# SCH_ESP-CellCore_USB_Interlock_RevA2_IMP.net
KiCad netlist of a schematic drawn in EasyEDA
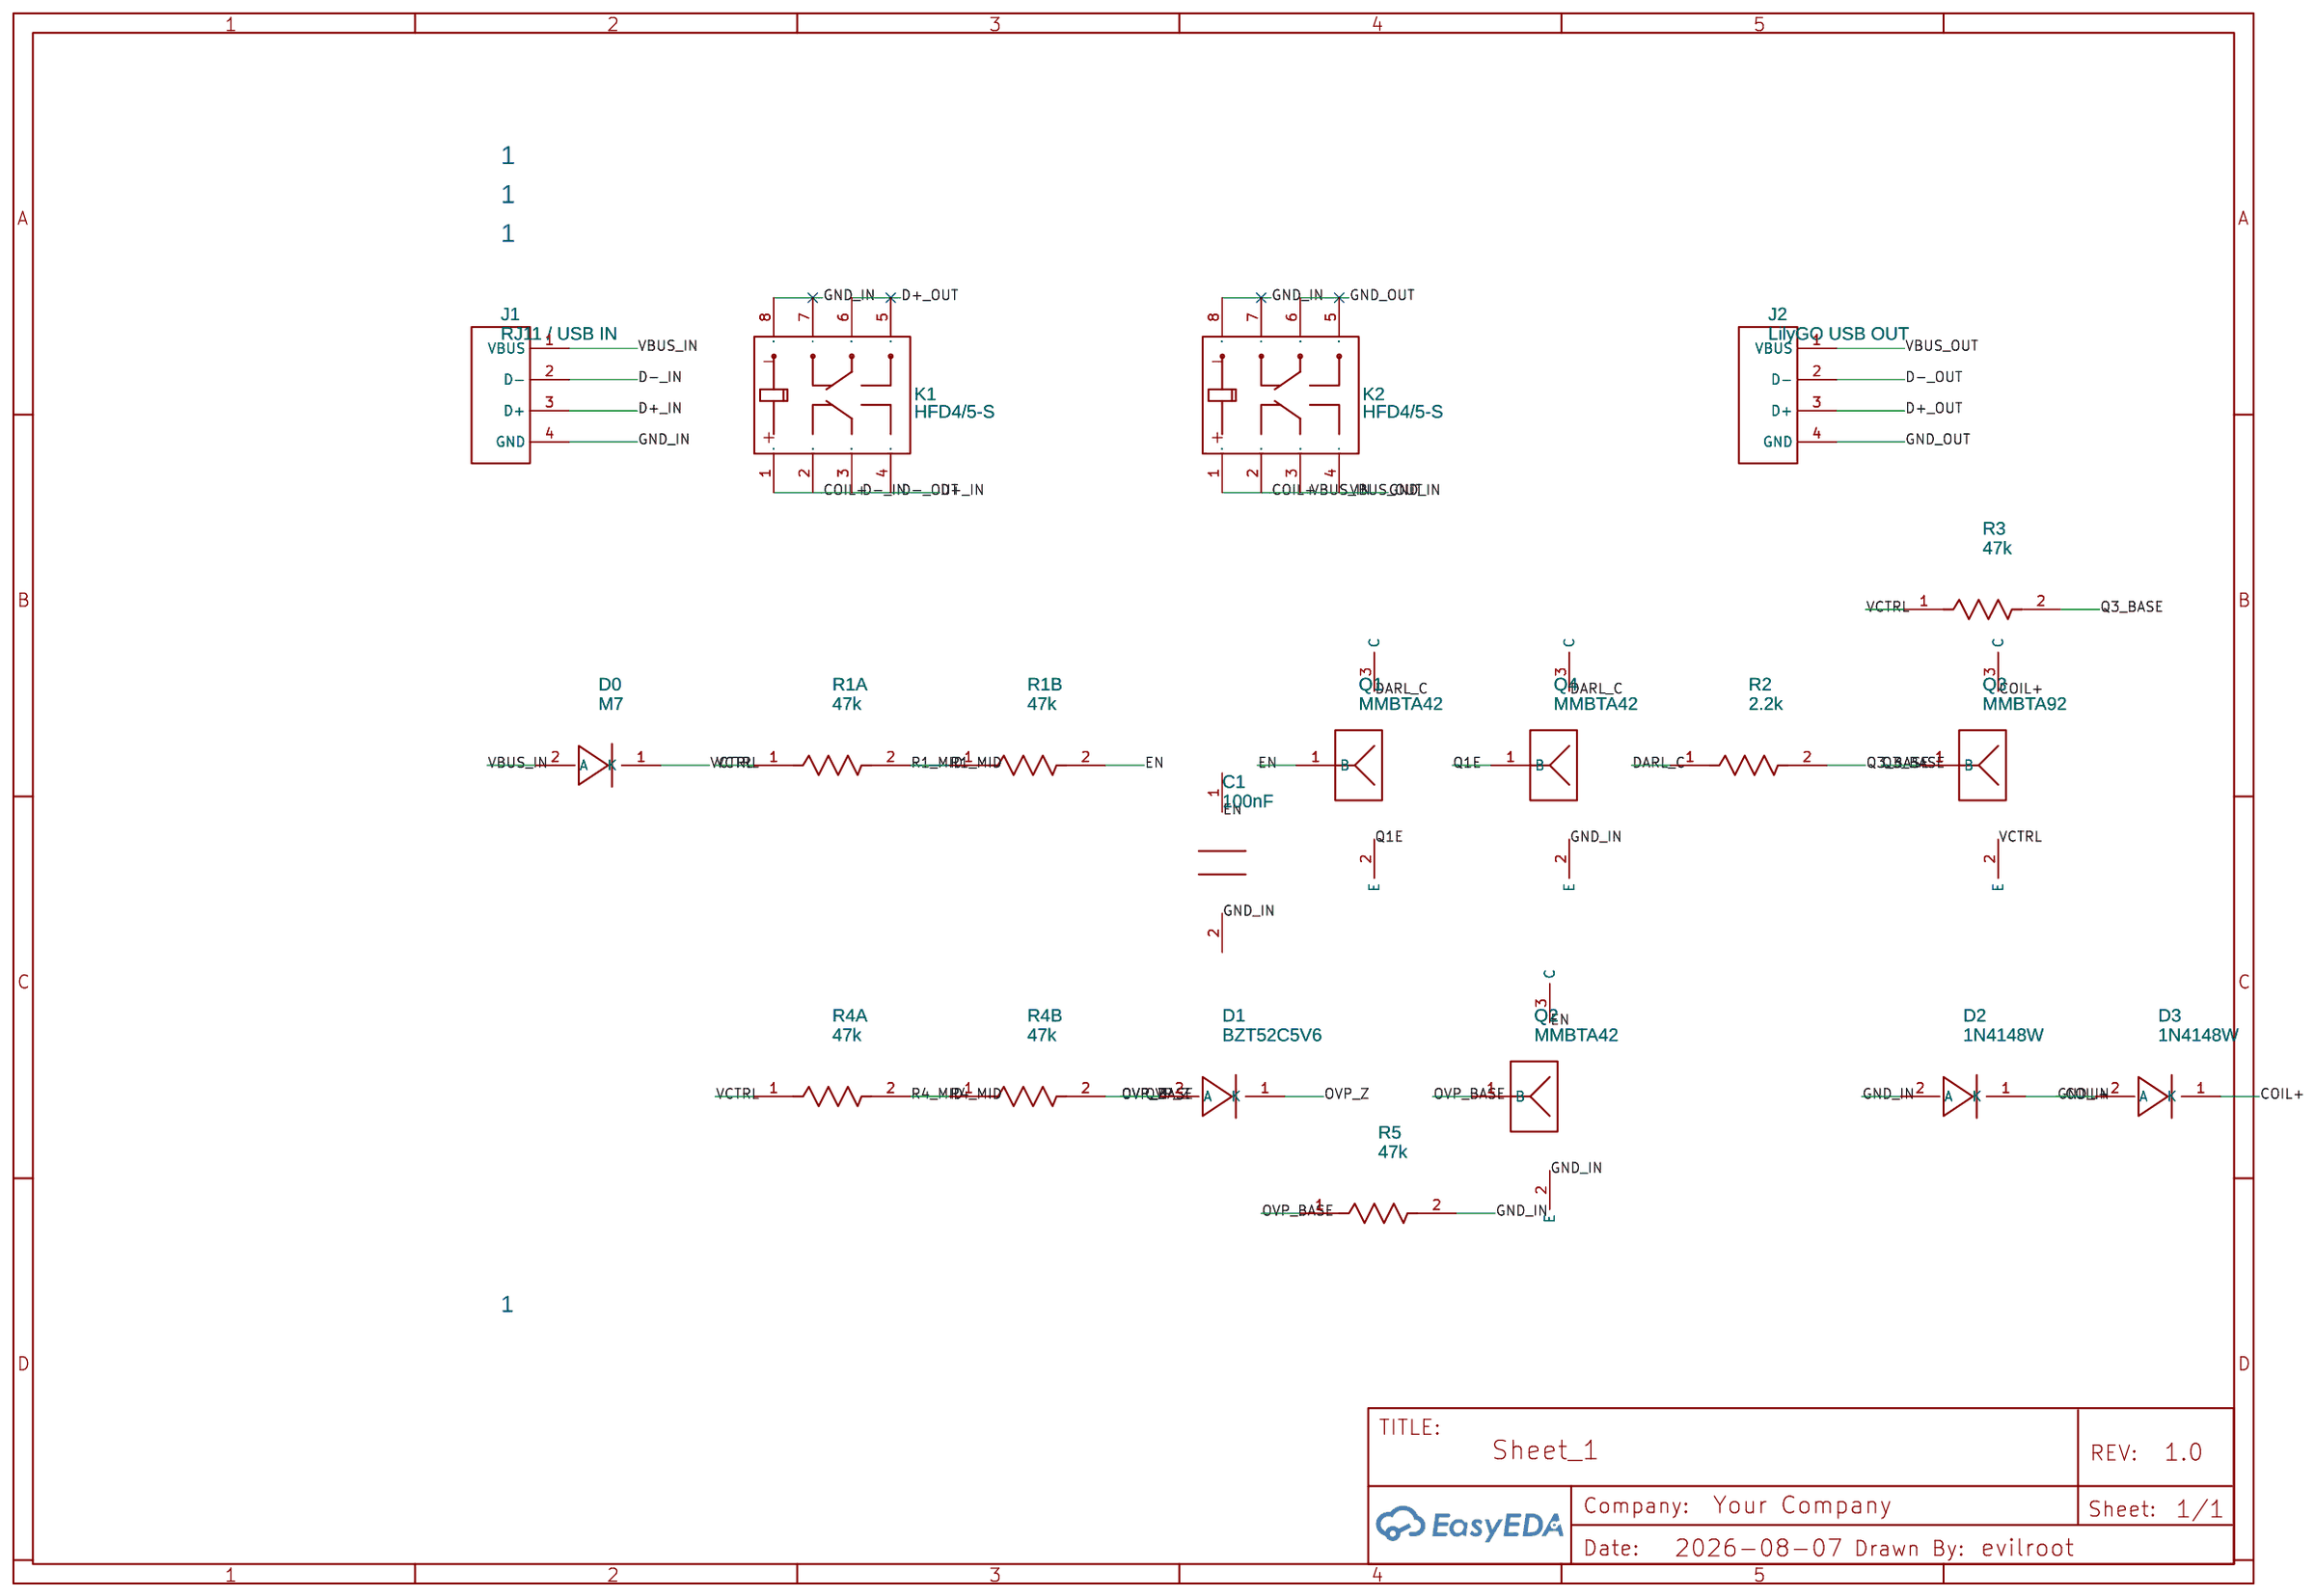
[diagram p0: schematic sheet]

(export (version "E")
  (design (tool "Eeschema 10.0.6"))
  (components
    (comp (ref "C1") (value "100nF") (libsource (lib "") (part "Unknown_620_-370")))
    (comp (ref "D0") (value "M7") (libsource (lib "") (part "Unknown_300_-420")))
    (comp (ref "D1") (value "BZT52C5V6") (libsource (lib "") (part "Unknown_620_-250")))
    (comp (ref "D2") (value "1N4148W") (libsource (lib "") (part "Unknown_1000_-250")))
    (comp (ref "D3") (value "1N4148W") (libsource (lib "") (part "Unknown_1100_-250")))
    (comp (ref "J1") (value "RJ11 / USB IN") (libsource (lib "") (part "Unknown_250_-610")))
    (comp (ref "J2") (value "LilyGO USB OUT") (libsource (lib "") (part "Unknown_900_-610")))
    (comp (ref "K1")
      (value "HFD4/5-S")
      (fields (field (name "Manufacturer Part") "HFD4/5-SR") (field (name "Manufacturer") "HF(宏发)"))
      (libsource (lib "") (part "HFD4/5-S"))
    )
    (comp (ref "K2")
      (value "HFD4/5-S")
      (fields (field (name "Manufacturer Part") "HFD4/5-SR") (field (name "Manufacturer") "HF(宏发)"))
      (libsource (lib "") (part "HFD4/5-S"))
    )
    (comp (ref "Q1") (value "MMBTA42") (libsource (lib "") (part "Unknown_690_-420")))
    (comp (ref "Q2") (value "MMBTA42") (libsource (lib "") (part "Unknown_780_-250")))
    (comp (ref "Q3") (value "MMBTA92") (libsource (lib "") (part "Unknown_1010_-420")))
    (comp (ref "Q4") (value "MMBTA42") (libsource (lib "") (part "Unknown_790_-420")))
    (comp (ref "R1A") (value "47k") (libsource (lib "") (part "Unknown_420_-420")))
    (comp (ref "R1B") (value "47k") (libsource (lib "") (part "Unknown_520_-420")))
    (comp (ref "R2") (value "2.2k") (libsource (lib "") (part "Unknown_890_-420")))
    (comp (ref "R3") (value "47k") (libsource (lib "") (part "Unknown_1010_-500")))
    (comp (ref "R4A") (value "47k") (libsource (lib "") (part "Unknown_420_-250")))
    (comp (ref "R4B") (value "47k") (libsource (lib "") (part "Unknown_520_-250")))
    (comp (ref "R5") (value "47k") (libsource (lib "") (part "Unknown_700_-190")))
  )
  (nets
    (net (code "1") (name "/COIL+") (class "Default")
      (node (ref "C1") (pin "2") (pintype "unspecified"))
      (node (ref "D0") (pin "2") (pinfunction "A_2") (pintype "unspecified"))
      (node (ref "D2") (pin "1") (pinfunction "K_1") (pintype "unspecified"))
      (node (ref "D2") (pin "2") (pinfunction "A_2") (pintype "unspecified"))
      (node (ref "D3") (pin "1") (pinfunction "K_1") (pintype "unspecified"))
      (node (ref "D3") (pin "2") (pinfunction "A_2") (pintype "unspecified"))
      (node (ref "J1") (pin "1") (pinfunction "VBUS_1") (pintype "unspecified"))
      (node (ref "J1") (pin "2") (pinfunction "D-_2") (pintype "unspecified"))
      (node (ref "J1") (pin "3") (pinfunction "D+_3") (pintype "unspecified"))
      (node (ref "J1") (pin "4") (pinfunction "GND_4") (pintype "unspecified"))
      (node (ref "J2") (pin "1") (pinfunction "VBUS_1") (pintype "unspecified"))
      (node (ref "J2") (pin "2") (pinfunction "D-_2") (pintype "unspecified"))
      (node (ref "K1") (pin "1") (pinfunction "1_1") (pintype "input"))
      (node (ref "K1") (pin "2") (pinfunction "2_2") (pintype "input"))
      (node (ref "K1") (pin "3") (pinfunction "3_3") (pintype "input"))
      (node (ref "K1") (pin "4") (pinfunction "4_4") (pintype "input"))
      (node (ref "K1") (pin "8") (pinfunction "8_8") (pintype "input"))
      (node (ref "K2") (pin "1") (pinfunction "1_1") (pintype "input"))
      (node (ref "K2") (pin "2") (pinfunction "2_2") (pintype "input"))
      (node (ref "K2") (pin "3") (pinfunction "3_3") (pintype "input"))
      (node (ref "K2") (pin "4") (pinfunction "4_4") (pintype "input"))
      (node (ref "K2") (pin "8") (pinfunction "8_8") (pintype "input"))
      (node (ref "Q2") (pin "2") (pinfunction "E_2") (pintype "unspecified"))
      (node (ref "Q3") (pin "3") (pinfunction "C_3") (pintype "unspecified"))
      (node (ref "Q4") (pin "2") (pinfunction "E_2") (pintype "unspecified"))
      (node (ref "R5") (pin "2") (pintype "unspecified"))
    )
    (net (code "2") (name "/D+_OUT") (class "Default")
      (node (ref "J2") (pin "3") (pinfunction "D+_3") (pintype "unspecified"))
      (node (ref "K1") (pin "6") (pinfunction "6_6") (pintype "input"))
    )
    (net (code "3") (name "/DARL_C") (class "Default")
      (node (ref "Q1") (pin "3") (pinfunction "C_3") (pintype "unspecified"))
      (node (ref "Q4") (pin "3") (pinfunction "C_3") (pintype "unspecified"))
      (node (ref "R2") (pin "1") (pintype "unspecified"))
    )
    (net (code "4") (name "/EN") (class "Default")
      (node (ref "C1") (pin "1") (pintype "unspecified"))
      (node (ref "Q1") (pin "1") (pinfunction "B_1") (pintype "unspecified"))
      (node (ref "Q2") (pin "3") (pinfunction "C_3") (pintype "unspecified"))
      (node (ref "R1B") (pin "2") (pintype "unspecified"))
    )
    (net (code "5") (name "/GND_OUT") (class "Default")
      (node (ref "J2") (pin "4") (pinfunction "GND_4") (pintype "unspecified"))
      (node (ref "K2") (pin "6") (pinfunction "6_6") (pintype "input"))
    )
    (net (code "6") (name "/OVP_BASE") (class "Default")
      (node (ref "D1") (pin "1") (pinfunction "K_1") (pintype "unspecified"))
      (node (ref "D1") (pin "2") (pinfunction "A_2") (pintype "unspecified"))
      (node (ref "Q2") (pin "1") (pinfunction "B_1") (pintype "unspecified"))
      (node (ref "R4B") (pin "2") (pintype "unspecified"))
      (node (ref "R5") (pin "1") (pintype "unspecified"))
    )
    (net (code "7") (name "/Q1E") (class "Default")
      (node (ref "Q1") (pin "2") (pinfunction "E_2") (pintype "unspecified"))
      (node (ref "Q4") (pin "1") (pinfunction "B_1") (pintype "unspecified"))
    )
    (net (code "8") (name "/Q3_BASE") (class "Default")
      (node (ref "Q3") (pin "1") (pinfunction "B_1") (pintype "unspecified"))
      (node (ref "R2") (pin "2") (pintype "unspecified"))
      (node (ref "R3") (pin "2") (pintype "unspecified"))
    )
    (net (code "9") (name "/R1_MID") (class "Default")
      (node (ref "R1A") (pin "2") (pintype "unspecified"))
      (node (ref "R1B") (pin "1") (pintype "unspecified"))
    )
    (net (code "10") (name "/R4_MID") (class "Default")
      (node (ref "R4A") (pin "2") (pintype "unspecified"))
      (node (ref "R4B") (pin "1") (pintype "unspecified"))
    )
    (net (code "11") (name "/VCTRL") (class "Default")
      (node (ref "D0") (pin "1") (pinfunction "K_1") (pintype "unspecified"))
      (node (ref "Q3") (pin "2") (pinfunction "E_2") (pintype "unspecified"))
      (node (ref "R1A") (pin "1") (pintype "unspecified"))
      (node (ref "R3") (pin "1") (pintype "unspecified"))
      (node (ref "R4A") (pin "1") (pintype "unspecified"))
    )
    (net (code "12") (name "unconnected-(K1-Pad5)") (class "Default")
      (node (ref "K1") (pin "5") (pinfunction "5_5") (pintype "input+no_connect"))
    )
    (net (code "13") (name "unconnected-(K1-Pad7)") (class "Default")
      (node (ref "K1") (pin "7") (pinfunction "7_7") (pintype "input+no_connect"))
    )
    (net (code "14") (name "unconnected-(K2-Pad5)") (class "Default")
      (node (ref "K2") (pin "5") (pinfunction "5_5") (pintype "input+no_connect"))
    )
    (net (code "15") (name "unconnected-(K2-Pad7)") (class "Default")
      (node (ref "K2") (pin "7") (pinfunction "7_7") (pintype "input+no_connect"))
    )
  )
)
